# led.net
KiCad netlist of a schematic drawn in EAGLE
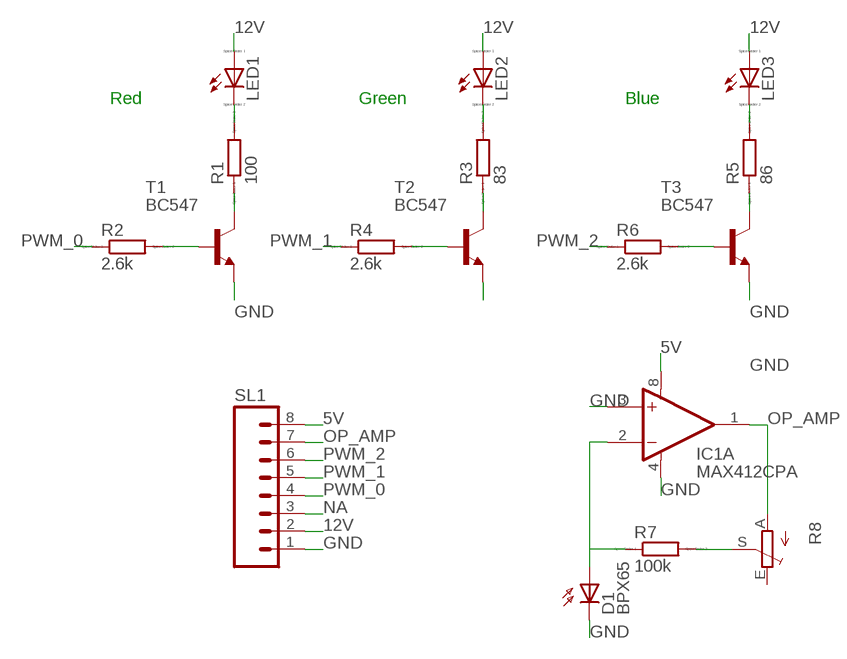
[diagram p0: schematic, sheet 1]

(export (version "E")
  (design (tool "Eeschema 10.0.6"))
  (components
    (comp (ref "D1")
      (value "BPX65")
      (footprint "eagle-import:BPX65")
      (fields (field (name "MPN") "BPX65."))
      (libsource (lib "eagle-import") (part "BPX65"))
    )
    (comp (ref "IC1")
      (value "MAX412CPA")
      (footprint "eagle-import:DIL08")
      (libsource (lib "eagle-import") (part "MAX412CPA"))
    )
    (comp (ref "LED1")
      (value "LED_ELD260")
      (footprint "eagle-import:LED_LD260")
      (libsource (lib "eagle-import") (part "LED_ELD260"))
    )
    (comp (ref "LED2")
      (value "LED_ELD260")
      (footprint "eagle-import:LED_LD260")
      (libsource (lib "eagle-import") (part "LED_ELD260"))
    )
    (comp (ref "LED3")
      (value "LED_ELD260")
      (footprint "eagle-import:LED_LD260")
      (libsource (lib "eagle-import") (part "LED_ELD260"))
    )
    (comp (ref "R1")
      (value "100")
      (footprint "eagle-import:0204_7")
      (libsource (lib "eagle-import") (part "R0204/7"))
    )
    (comp (ref "R2")
      (value "2.6k")
      (footprint "eagle-import:0204_7")
      (libsource (lib "eagle-import") (part "R0204/7"))
    )
    (comp (ref "R3")
      (value "83")
      (footprint "eagle-import:0204_7")
      (libsource (lib "eagle-import") (part "R0204/7"))
    )
    (comp (ref "R4")
      (value "2.6k")
      (footprint "eagle-import:0204_7")
      (libsource (lib "eagle-import") (part "R0204/7"))
    )
    (comp (ref "R5")
      (value "86")
      (footprint "eagle-import:0204_7")
      (libsource (lib "eagle-import") (part "R0204/7"))
    )
    (comp (ref "R6")
      (value "2.6k")
      (footprint "eagle-import:0204_7")
      (libsource (lib "eagle-import") (part "R0204/7"))
    )
    (comp (ref "R7")
      (value "100k")
      (footprint "eagle-import:0204_7")
      (libsource (lib "eagle-import") (part "R0204/7"))
    )
    (comp (ref "R8")
      (value "TRIM_EU-B90P")
      (footprint "eagle-import:SP19L")
      (libsource (lib "eagle-import") (part "TRIM_EU-B90P"))
    )
    (comp (ref "SL1")
      (value "M08")
      (footprint "eagle-import:08P")
      (libsource (lib "eagle-import") (part "M08"))
    )
    (comp (ref "T1")
      (value "BC547")
      (footprint "eagle-import:TO92")
      (libsource (lib "eagle-import") (part "BC547"))
    )
    (comp (ref "T2")
      (value "BC547")
      (footprint "eagle-import:TO92")
      (libsource (lib "eagle-import") (part "BC547"))
    )
    (comp (ref "T3")
      (value "BC547")
      (footprint "eagle-import:TO92")
      (libsource (lib "eagle-import") (part "BC547"))
    )
  )
  (nets
    (net (code "1") (name "/5V") (class "Default")
      (node (ref "IC1") (pin "8") (pinfunction "V+_8") (pintype "power_in"))
      (node (ref "SL1") (pin "8") (pinfunction "8_8") (pintype "passive"))
    )
    (net (code "2") (name "/12V") (class "Default")
      (node (ref "LED1") (pin "A") (pinfunction "A_A") (pintype "passive"))
      (node (ref "LED2") (pin "A") (pinfunction "A_A") (pintype "passive"))
      (node (ref "LED3") (pin "A") (pinfunction "A_A") (pintype "passive"))
      (node (ref "SL1") (pin "2") (pinfunction "2_2") (pintype "passive"))
    )
    (net (code "3") (name "/GND") (class "Default")
      (node (ref "D1") (pin "K") (pinfunction "C_K") (pintype "passive"))
      (node (ref "IC1") (pin "3") (pinfunction "+IN_3") (pintype "input"))
      (node (ref "IC1") (pin "4") (pinfunction "V-_4") (pintype "power_in"))
      (node (ref "SL1") (pin "1") (pinfunction "1_1") (pintype "passive"))
      (node (ref "T1") (pin "1") (pinfunction "E_1") (pintype "passive"))
      (node (ref "T2") (pin "1") (pinfunction "E_1") (pintype "passive"))
      (node (ref "T3") (pin "1") (pinfunction "E_1") (pintype "passive"))
    )
    (net (code "4") (name "/NA") (class "Default")
      (node (ref "SL1") (pin "3") (pinfunction "3_3") (pintype "passive"))
    )
    (net (code "5") (name "/OP_AMP") (class "Default")
      (node (ref "IC1") (pin "1") (pinfunction "OUT_1") (pintype "output"))
      (node (ref "R8") (pin "A") (pinfunction "A_A") (pintype "passive"))
      (node (ref "SL1") (pin "7") (pinfunction "7_7") (pintype "passive"))
    )
    (net (code "6") (name "/PWM_0") (class "Default")
      (node (ref "R2") (pin "1") (pinfunction "1_1") (pintype "passive"))
      (node (ref "SL1") (pin "4") (pinfunction "4_4") (pintype "passive"))
    )
    (net (code "7") (name "/PWM_1") (class "Default")
      (node (ref "R4") (pin "1") (pinfunction "1_1") (pintype "passive"))
      (node (ref "SL1") (pin "5") (pinfunction "5_5") (pintype "passive"))
    )
    (net (code "8") (name "/PWM_2") (class "Default")
      (node (ref "R6") (pin "1") (pinfunction "1_1") (pintype "passive"))
      (node (ref "SL1") (pin "6") (pinfunction "6_6") (pintype "passive"))
    )
    (net (code "9") (name "Net-(IC1A--IN)") (class "Default")
      (node (ref "D1") (pin "A") (pinfunction "A_A") (pintype "passive"))
      (node (ref "IC1") (pin "2") (pinfunction "-IN_2") (pintype "input"))
      (node (ref "R7") (pin "1") (pinfunction "1_1") (pintype "passive"))
    )
    (net (code "10") (name "Net-(LED1-C)") (class "Default")
      (node (ref "LED1") (pin "K") (pinfunction "C_K") (pintype "passive"))
      (node (ref "R1") (pin "2") (pinfunction "2_2") (pintype "passive"))
    )
    (net (code "11") (name "Net-(LED2-C)") (class "Default")
      (node (ref "LED2") (pin "K") (pinfunction "C_K") (pintype "passive"))
      (node (ref "R3") (pin "2") (pinfunction "2_2") (pintype "passive"))
    )
    (net (code "12") (name "Net-(LED3-C)") (class "Default")
      (node (ref "LED3") (pin "K") (pinfunction "C_K") (pintype "passive"))
      (node (ref "R5") (pin "2") (pinfunction "2_2") (pintype "passive"))
    )
    (net (code "13") (name "Net-(R7-Pad2)") (class "Default")
      (node (ref "R7") (pin "2") (pinfunction "2_2") (pintype "passive"))
      (node (ref "R8") (pin "S") (pinfunction "S_S") (pintype "passive"))
    )
    (net (code "14") (name "Net-(T1-B)") (class "Default")
      (node (ref "R2") (pin "2") (pinfunction "2_2") (pintype "passive"))
      (node (ref "T1") (pin "2") (pinfunction "B_2") (pintype "passive"))
    )
    (net (code "15") (name "Net-(T1-C)") (class "Default")
      (node (ref "R1") (pin "1") (pinfunction "1_1") (pintype "passive"))
      (node (ref "T1") (pin "3") (pinfunction "C_3") (pintype "passive"))
    )
    (net (code "16") (name "Net-(T2-B)") (class "Default")
      (node (ref "R4") (pin "2") (pinfunction "2_2") (pintype "passive"))
      (node (ref "T2") (pin "2") (pinfunction "B_2") (pintype "passive"))
    )
    (net (code "17") (name "Net-(T2-C)") (class "Default")
      (node (ref "R3") (pin "1") (pinfunction "1_1") (pintype "passive"))
      (node (ref "T2") (pin "3") (pinfunction "C_3") (pintype "passive"))
    )
    (net (code "18") (name "Net-(T3-B)") (class "Default")
      (node (ref "R6") (pin "2") (pinfunction "2_2") (pintype "passive"))
      (node (ref "T3") (pin "2") (pinfunction "B_2") (pintype "passive"))
    )
    (net (code "19") (name "Net-(T3-C)") (class "Default")
      (node (ref "R5") (pin "1") (pinfunction "1_1") (pintype "passive"))
      (node (ref "T3") (pin "3") (pinfunction "C_3") (pintype "passive"))
    )
    (net (code "20") (name "unconnected-(R8-PadE)") (class "Default")
      (node (ref "R8") (pin "E") (pinfunction "E_E") (pintype "passive"))
    )
  )
)
